# CAN.net
KiCad netlist of a schematic drawn in Altium Designer
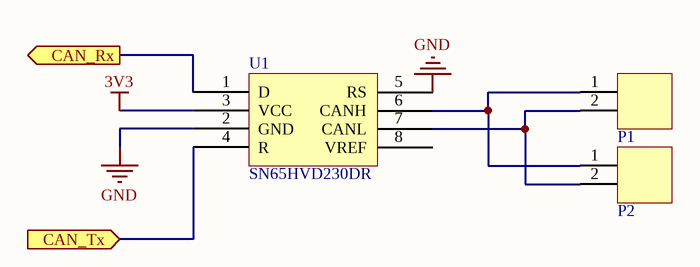
[diagram p0: CAN.SchDoc]

(export (version "E")
  (design (tool "Eeschema 10.0.6"))
  (components
    (comp (ref "P1")
      (value "2-pin Horz Sherlock")
      (footprint "MOLEX-HDR-1X2-SHERLOCK-HORZ")
      (fields
        (field (name "MANUFACTURER PART NUMBER") "0353630260")
        (field (name "MANUFACTURER") "Molex Inc")
      )
      (libsource (lib "SubjuGator8") (part "MOLEX-HDR-1x2-SHERLOCK_RA"))
    )
    (comp (ref "P2")
      (value "2-pin Horz Sherlock")
      (footprint "MOLEX-HDR-1X2-SHERLOCK-HORZ")
      (fields
        (field (name "MANUFACTURER PART NUMBER") "0353630260")
        (field (name "MANUFACTURER") "Molex Inc")
      )
      (libsource (lib "SubjuGator8") (part "MOLEX-HDR-1x2-SHERLOCK_RA"))
    )
    (comp (ref "U1")
      (value "SN65HVD230DR")
      (footprint "SOIC-8pin")
      (description "IC TXRX CAN 1MBPS 3.3V 8SOIC")
      (libsource (lib "SubjuGator8") (part "SN65HVD230DR"))
    )
  )
  (nets
    (net (code "1") (name "/CAN_Rx") (class "Default")
      (node (ref "U1") (pin "1") (pinfunction "D_1") (pintype "passive"))
    )
    (net (code "2") (name "/CAN_Tx") (class "Default")
      (node (ref "U1") (pin "4") (pinfunction "R_4") (pintype "passive"))
    )
    (net (code "3") (name "3V3") (class "Default")
      (node (ref "U1") (pin "3") (pinfunction "VCC_3") (pintype "passive"))
    )
    (net (code "4") (name "GND") (class "Default")
      (node (ref "U1") (pin "2") (pinfunction "GND_2") (pintype "passive"))
      (node (ref "U1") (pin "5") (pinfunction "RS_5") (pintype "passive"))
    )
    (net (code "5") (name "Net-(U1-CANH)") (class "Default")
      (node (ref "P1") (pin "1") (pinfunction "1_1") (pintype "passive"))
      (node (ref "P2") (pin "1") (pinfunction "1_1") (pintype "passive"))
      (node (ref "U1") (pin "6") (pinfunction "CANH_6") (pintype "passive"))
    )
    (net (code "6") (name "Net-(U1-CANL)") (class "Default")
      (node (ref "P1") (pin "2") (pinfunction "2_2") (pintype "passive"))
      (node (ref "P2") (pin "2") (pinfunction "2_2") (pintype "passive"))
      (node (ref "U1") (pin "7") (pinfunction "CANL_7") (pintype "passive"))
    )
    (net (code "7") (name "unconnected-(U1-VREF-Pad8)") (class "Default")
      (node (ref "U1") (pin "8") (pinfunction "VREF_8") (pintype "passive"))
    )
  )
)
